# Connector.net
KiCad netlist of a schematic drawn in Altium Designer
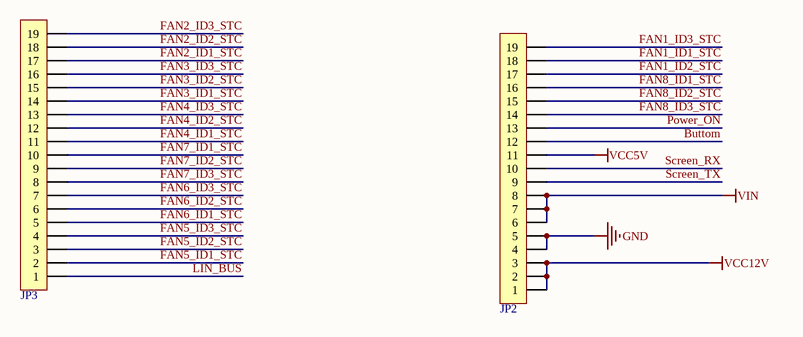
[diagram p0: Connector.SchDoc]

(export (version "E")
  (design (tool "Eeschema 10.0.6"))
  (components
    (comp (ref "JP2")
      (value "HDR-1X19")
      (footprint "贴片排母2.54mm_交错_19P")
      (description "19P接插件")
      (fields (field (name "版权归属") "源创客"))
      (libsource (lib "Connector-PinHeader") (part "Header 19"))
    )
    (comp (ref "JP3")
      (value "HDR-1X19")
      (footprint "贴片排母2.54mm_交错_19P")
      (description "19P接插件")
      (fields (field (name "版权归属") "源创客"))
      (libsource (lib "Connector-PinHeader") (part "Header 19"))
    )
  )
  (nets
    (net (code "1") (name "/Buttom") (class "Default")
      (node (ref "JP2") (pin "12") (pinfunction "12_12") (pintype "passive"))
    )
    (net (code "2") (name "/FAN1_ID1_STC") (class "Default")
      (node (ref "JP2") (pin "18") (pinfunction "18_18") (pintype "passive"))
    )
    (net (code "3") (name "/FAN1_ID2_STC") (class "Default")
      (node (ref "JP2") (pin "17") (pinfunction "17_17") (pintype "passive"))
    )
    (net (code "4") (name "/FAN1_ID3_STC") (class "Default")
      (node (ref "JP2") (pin "19") (pinfunction "19_19") (pintype "passive"))
    )
    (net (code "5") (name "/FAN2_ID1_STC") (class "Default")
      (node (ref "JP3") (pin "17") (pinfunction "17_17") (pintype "passive"))
    )
    (net (code "6") (name "/FAN2_ID2_STC") (class "Default")
      (node (ref "JP3") (pin "18") (pinfunction "18_18") (pintype "passive"))
    )
    (net (code "7") (name "/FAN2_ID3_STC") (class "Default")
      (node (ref "JP3") (pin "19") (pinfunction "19_19") (pintype "passive"))
    )
    (net (code "8") (name "/FAN3_ID1_STC") (class "Default")
      (node (ref "JP3") (pin "14") (pinfunction "14_14") (pintype "passive"))
    )
    (net (code "9") (name "/FAN3_ID2_STC") (class "Default")
      (node (ref "JP3") (pin "15") (pinfunction "15_15") (pintype "passive"))
    )
    (net (code "10") (name "/FAN3_ID3_STC") (class "Default")
      (node (ref "JP3") (pin "16") (pinfunction "16_16") (pintype "passive"))
    )
    (net (code "11") (name "/FAN4_ID1_STC") (class "Default")
      (node (ref "JP3") (pin "11") (pinfunction "11_11") (pintype "passive"))
    )
    (net (code "12") (name "/FAN4_ID2_STC") (class "Default")
      (node (ref "JP3") (pin "12") (pinfunction "12_12") (pintype "passive"))
    )
    (net (code "13") (name "/FAN4_ID3_STC") (class "Default")
      (node (ref "JP3") (pin "13") (pinfunction "13_13") (pintype "passive"))
    )
    (net (code "14") (name "/FAN5_ID1_STC") (class "Default")
      (node (ref "JP3") (pin "2") (pinfunction "2_2") (pintype "passive"))
    )
    (net (code "15") (name "/FAN5_ID2_STC") (class "Default")
      (node (ref "JP3") (pin "3") (pinfunction "3_3") (pintype "passive"))
    )
    (net (code "16") (name "/FAN5_ID3_STC") (class "Default")
      (node (ref "JP3") (pin "4") (pinfunction "4_4") (pintype "passive"))
    )
    (net (code "17") (name "/FAN6_ID1_STC") (class "Default")
      (node (ref "JP3") (pin "5") (pinfunction "5_5") (pintype "passive"))
    )
    (net (code "18") (name "/FAN6_ID2_STC") (class "Default")
      (node (ref "JP3") (pin "6") (pinfunction "6_6") (pintype "passive"))
    )
    (net (code "19") (name "/FAN6_ID3_STC") (class "Default")
      (node (ref "JP3") (pin "7") (pinfunction "7_7") (pintype "passive"))
    )
    (net (code "20") (name "/FAN7_ID1_STC") (class "Default")
      (node (ref "JP3") (pin "10") (pinfunction "10_10") (pintype "passive"))
    )
    (net (code "21") (name "/FAN7_ID2_STC") (class "Default")
      (node (ref "JP3") (pin "9") (pinfunction "9_9") (pintype "passive"))
    )
    (net (code "22") (name "/FAN7_ID3_STC") (class "Default")
      (node (ref "JP3") (pin "8") (pinfunction "8_8") (pintype "passive"))
    )
    (net (code "23") (name "/FAN8_ID1_STC") (class "Default")
      (node (ref "JP2") (pin "16") (pinfunction "16_16") (pintype "passive"))
    )
    (net (code "24") (name "/FAN8_ID2_STC") (class "Default")
      (node (ref "JP2") (pin "15") (pinfunction "15_15") (pintype "passive"))
    )
    (net (code "25") (name "/FAN8_ID3_STC") (class "Default")
      (node (ref "JP2") (pin "14") (pinfunction "14_14") (pintype "passive"))
    )
    (net (code "26") (name "/LIN_BUS") (class "Default")
      (node (ref "JP3") (pin "1") (pinfunction "1_1") (pintype "passive"))
    )
    (net (code "27") (name "/Power_ON") (class "Default")
      (node (ref "JP2") (pin "13") (pinfunction "13_13") (pintype "passive"))
    )
    (net (code "28") (name "/Screen_RX") (class "Default")
      (node (ref "JP2") (pin "10") (pinfunction "10_10") (pintype "passive"))
    )
    (net (code "29") (name "/Screen_TX") (class "Default")
      (node (ref "JP2") (pin "9") (pinfunction "9_9") (pintype "passive"))
    )
    (net (code "30") (name "GND") (class "Default")
      (node (ref "JP2") (pin "4") (pinfunction "4_4") (pintype "passive"))
      (node (ref "JP2") (pin "5") (pinfunction "5_5") (pintype "passive"))
    )
    (net (code "31") (name "VCC5V") (class "Default")
      (node (ref "JP2") (pin "11") (pinfunction "11_11") (pintype "passive"))
    )
    (net (code "32") (name "VCC12V") (class "Default")
      (node (ref "JP2") (pin "1") (pinfunction "1_1") (pintype "passive"))
      (node (ref "JP2") (pin "2") (pinfunction "2_2") (pintype "passive"))
      (node (ref "JP2") (pin "3") (pinfunction "3_3") (pintype "passive"))
    )
    (net (code "33") (name "VIN") (class "Default")
      (node (ref "JP2") (pin "6") (pinfunction "6_6") (pintype "passive"))
      (node (ref "JP2") (pin "7") (pinfunction "7_7") (pintype "passive"))
      (node (ref "JP2") (pin "8") (pinfunction "8_8") (pintype "passive"))
    )
  )
)
